# FUC.net
KiCad netlist of a schematic drawn in Altium Designer
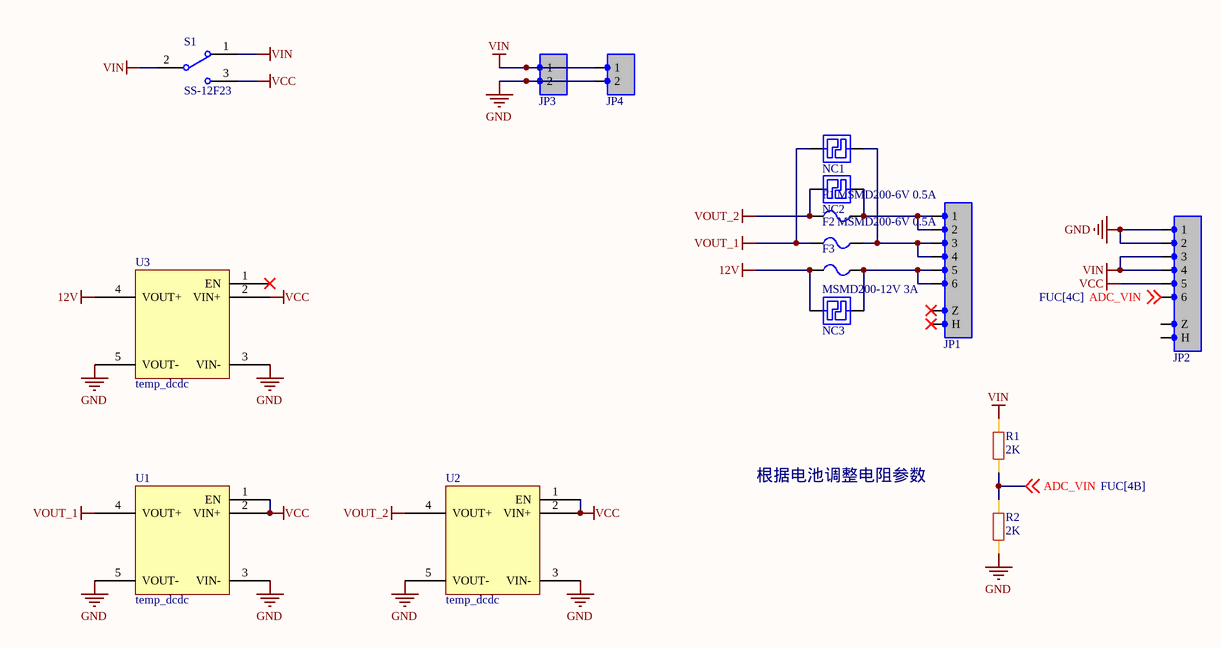
[diagram p0: FUC.SchDoc]

(export (version "E")
  (design (tool "Eeschema 10.0.6"))
  (components
    (comp (ref "F1")
      (value "MSMD200-6V 0.5A")
      (footprint "FU 0805")
      (description "贴片保险丝")
      (fields (field (name "版权归属") "源创客"))
      (libsource (lib "6.3-保险丝") (part "FU"))
    )
    (comp (ref "F2")
      (value "MSMD200-6V 0.5A")
      (footprint "FU 0805")
      (description "贴片保险丝")
      (fields (field (name "版权归属") "源创客"))
      (libsource (lib "6.3-保险丝") (part "FU"))
    )
    (comp (ref "F3")
      (value "MSMD200-12V 3A")
      (footprint "FU 0805")
      (description "贴片保险丝")
      (fields (field (name "版权归属") "源创客"))
      (libsource (lib "6.3-保险丝") (part "FU"))
    )
    (comp (ref "JP1")
      (value "HDR-1X6")
      (footprint "HDR2.54-LI-6P")
      (description "6P接插件")
      (fields (field (name "版权归属") "源创客"))
      (libsource (lib "14.6-接插件-脚距2.54") (part "Header 6"))
    )
    (comp (ref "JP2")
      (value "HDR-1X6")
      (footprint "HDR2.54-LI-6P")
      (description "6P接插件")
      (fields (field (name "版权归属") "源创客"))
      (libsource (lib "14.6-接插件-脚距2.54") (part "Header 6"))
    )
    (comp (ref "JP3")
      (value "HDR-1X2")
      (footprint "XH2.54-WI-2P")
      (description "2P接插件")
      (fields (field (name "版权归属") "源创客"))
      (libsource (lib "14.6-接插件-脚距2.54") (part "Header 2"))
    )
    (comp (ref "JP4")
      (value "HDR-1X2")
      (footprint "HDR2.54-LI-2P")
      (description "2P接插件")
      (fields (field (name "版权归属") "源创客"))
      (libsource (lib "14.6-接插件-脚距2.54") (part "Header 2"))
    )
    (comp (ref "NC1")
      (value "Node")
      (footprint "NODE-2")
      (description "大电流节点")
      (libsource (lib "13.1-未分类器件") (part "NODE"))
    )
    (comp (ref "NC2")
      (value "Node")
      (footprint "NODE-2")
      (description "大电流节点")
      (libsource (lib "13.1-未分类器件") (part "NODE"))
    )
    (comp (ref "NC3")
      (value "Node")
      (footprint "NODE-2")
      (description "大电流节点")
      (libsource (lib "13.1-未分类器件") (part "NODE"))
    )
    (comp (ref "R1")
      (value "2K")
      (footprint "R 0603_L")
      (description "贴片电阻1%精度")
      (libsource (lib "Propitious Clouds_SCHLIB") (part "电阻"))
    )
    (comp (ref "R2")
      (value "2K")
      (footprint "R 0603_L")
      (description "贴片电阻1%精度")
      (libsource (lib "Propitious Clouds_SCHLIB") (part "电阻"))
    )
    (comp (ref "S1")
      (value "SS-12F23")
      (footprint "SS-12D10")
      (description "1路拨动开关")
      (fields (field (name "版权归属") "源创客"))
      (libsource (lib "6.2-开关") (part "SSW-1P"))
    )
    (comp (ref "U1")
      (value "temp_dcdc")
      (footprint "TEMP_DCDC")
      (description "升降压模块")
      (libsource (lib "userLib") (part "temp_dcdc"))
    )
    (comp (ref "U2")
      (value "temp_dcdc")
      (footprint "TEMP_DCDC")
      (description "升降压模块")
      (libsource (lib "userLib") (part "temp_dcdc"))
    )
    (comp (ref "U3")
      (value "temp_dcdc")
      (footprint "TEMP_12V")
      (description "升降压模块")
      (libsource (lib "userLib") (part "temp_dcdc"))
    )
  )
  (nets
    (net (code "1") (name "12V") (class "Default")
      (node (ref "F3") (pin "2") (pinfunction "2_2") (pintype "passive"))
      (node (ref "NC3") (pin "1") (pinfunction "1_1") (pintype "passive"))
      (node (ref "U3") (pin "4") (pinfunction "VOUT+_4") (pintype "passive"))
    )
    (net (code "2") (name "ADC_VIN") (class "Default")
      (node (ref "JP2") (pin "6") (pinfunction "6_6") (pintype "passive"))
      (node (ref "R1") (pin "2") (pinfunction "2_2") (pintype "passive"))
      (node (ref "R2") (pin "1") (pinfunction "1_1") (pintype "passive"))
    )
    (net (code "3") (name "GND") (class "Default")
      (node (ref "JP2") (pin "1") (pinfunction "1_1") (pintype "passive"))
      (node (ref "JP2") (pin "2") (pinfunction "2_2") (pintype "passive"))
      (node (ref "JP3") (pin "2") (pinfunction "2_2") (pintype "passive"))
      (node (ref "JP4") (pin "2") (pinfunction "2_2") (pintype "passive"))
      (node (ref "R2") (pin "2") (pinfunction "2_2") (pintype "passive"))
      (node (ref "U1") (pin "3") (pinfunction "VIN-_3") (pintype "passive"))
      (node (ref "U1") (pin "5") (pinfunction "VOUT-_5") (pintype "passive"))
      (node (ref "U2") (pin "3") (pinfunction "VIN-_3") (pintype "passive"))
      (node (ref "U2") (pin "5") (pinfunction "VOUT-_5") (pintype "passive"))
      (node (ref "U3") (pin "3") (pinfunction "VIN-_3") (pintype "passive"))
      (node (ref "U3") (pin "5") (pinfunction "VOUT-_5") (pintype "passive"))
    )
    (net (code "4") (name "Net-(F1-Pad2)") (class "Default")
      (node (ref "F1") (pin "2") (pinfunction "2_2") (pintype "passive"))
      (node (ref "JP1") (pin "1") (pinfunction "1_1") (pintype "passive"))
      (node (ref "JP1") (pin "2") (pinfunction "2_2") (pintype "passive"))
      (node (ref "NC2") (pin "2") (pinfunction "2_2") (pintype "passive"))
    )
    (net (code "5") (name "Net-(F2-Pad2)") (class "Default")
      (node (ref "F2") (pin "2") (pinfunction "2_2") (pintype "passive"))
      (node (ref "JP1") (pin "3") (pinfunction "3_3") (pintype "passive"))
      (node (ref "JP1") (pin "4") (pinfunction "4_4") (pintype "passive"))
      (node (ref "NC1") (pin "2") (pinfunction "2_2") (pintype "passive"))
    )
    (net (code "6") (name "Net-(F3-Pad1)") (class "Default")
      (node (ref "F3") (pin "1") (pinfunction "1_1") (pintype "passive"))
      (node (ref "JP1") (pin "5") (pinfunction "5_5") (pintype "passive"))
      (node (ref "JP1") (pin "6") (pinfunction "6_6") (pintype "passive"))
      (node (ref "NC3") (pin "2") (pinfunction "2_2") (pintype "passive"))
    )
    (net (code "7") (name "VCC") (class "Default")
      (node (ref "JP2") (pin "5") (pinfunction "5_5") (pintype "passive"))
      (node (ref "S1") (pin "3") (pinfunction "3_3") (pintype "passive"))
      (node (ref "U1") (pin "1") (pinfunction "EN_1") (pintype "passive"))
      (node (ref "U1") (pin "2") (pinfunction "VIN+_2") (pintype "passive"))
      (node (ref "U2") (pin "1") (pinfunction "EN_1") (pintype "passive"))
      (node (ref "U2") (pin "2") (pinfunction "VIN+_2") (pintype "passive"))
      (node (ref "U3") (pin "2") (pinfunction "VIN+_2") (pintype "passive"))
    )
    (net (code "8") (name "VIN") (class "Default")
      (node (ref "JP2") (pin "3") (pinfunction "3_3") (pintype "passive"))
      (node (ref "JP2") (pin "4") (pinfunction "4_4") (pintype "passive"))
      (node (ref "JP3") (pin "1") (pinfunction "1_1") (pintype "passive"))
      (node (ref "JP4") (pin "1") (pinfunction "1_1") (pintype "passive"))
      (node (ref "R1") (pin "1") (pinfunction "1_1") (pintype "passive"))
      (node (ref "S1") (pin "1") (pinfunction "1_1") (pintype "passive"))
      (node (ref "S1") (pin "2") (pinfunction "2_2") (pintype "passive"))
    )
    (net (code "9") (name "VOUT_1") (class "Default")
      (node (ref "F2") (pin "1") (pinfunction "1_1") (pintype "passive"))
      (node (ref "NC1") (pin "1") (pinfunction "1_1") (pintype "passive"))
      (node (ref "U1") (pin "4") (pinfunction "VOUT+_4") (pintype "passive"))
    )
    (net (code "10") (name "VOUT_2") (class "Default")
      (node (ref "F1") (pin "1") (pinfunction "1_1") (pintype "passive"))
      (node (ref "NC2") (pin "1") (pinfunction "1_1") (pintype "passive"))
      (node (ref "U2") (pin "4") (pinfunction "VOUT+_4") (pintype "passive"))
    )
    (net (code "11") (name "unconnected-(JP1-H-Pad100)") (class "Default")
      (node (ref "JP1") (pin "100") (pinfunction "H_100") (pintype "passive+no_connect"))
    )
    (net (code "12") (name "unconnected-(JP1-Z-Pad0)") (class "Default")
      (node (ref "JP1") (pin "0") (pinfunction "Z_0") (pintype "passive+no_connect"))
    )
    (net (code "13") (name "unconnected-(JP2-H-Pad100)") (class "Default")
      (node (ref "JP2") (pin "100") (pinfunction "H_100") (pintype "passive"))
    )
    (net (code "14") (name "unconnected-(JP2-Z-Pad0)") (class "Default")
      (node (ref "JP2") (pin "0") (pinfunction "Z_0") (pintype "passive"))
    )
    (net (code "15") (name "unconnected-(U3-EN-Pad1)") (class "Default")
      (node (ref "U3") (pin "1") (pinfunction "EN_1") (pintype "passive+no_connect"))
    )
  )
)
